# Portier.net
KiCad netlist of a schematic drawn in Altium Designer
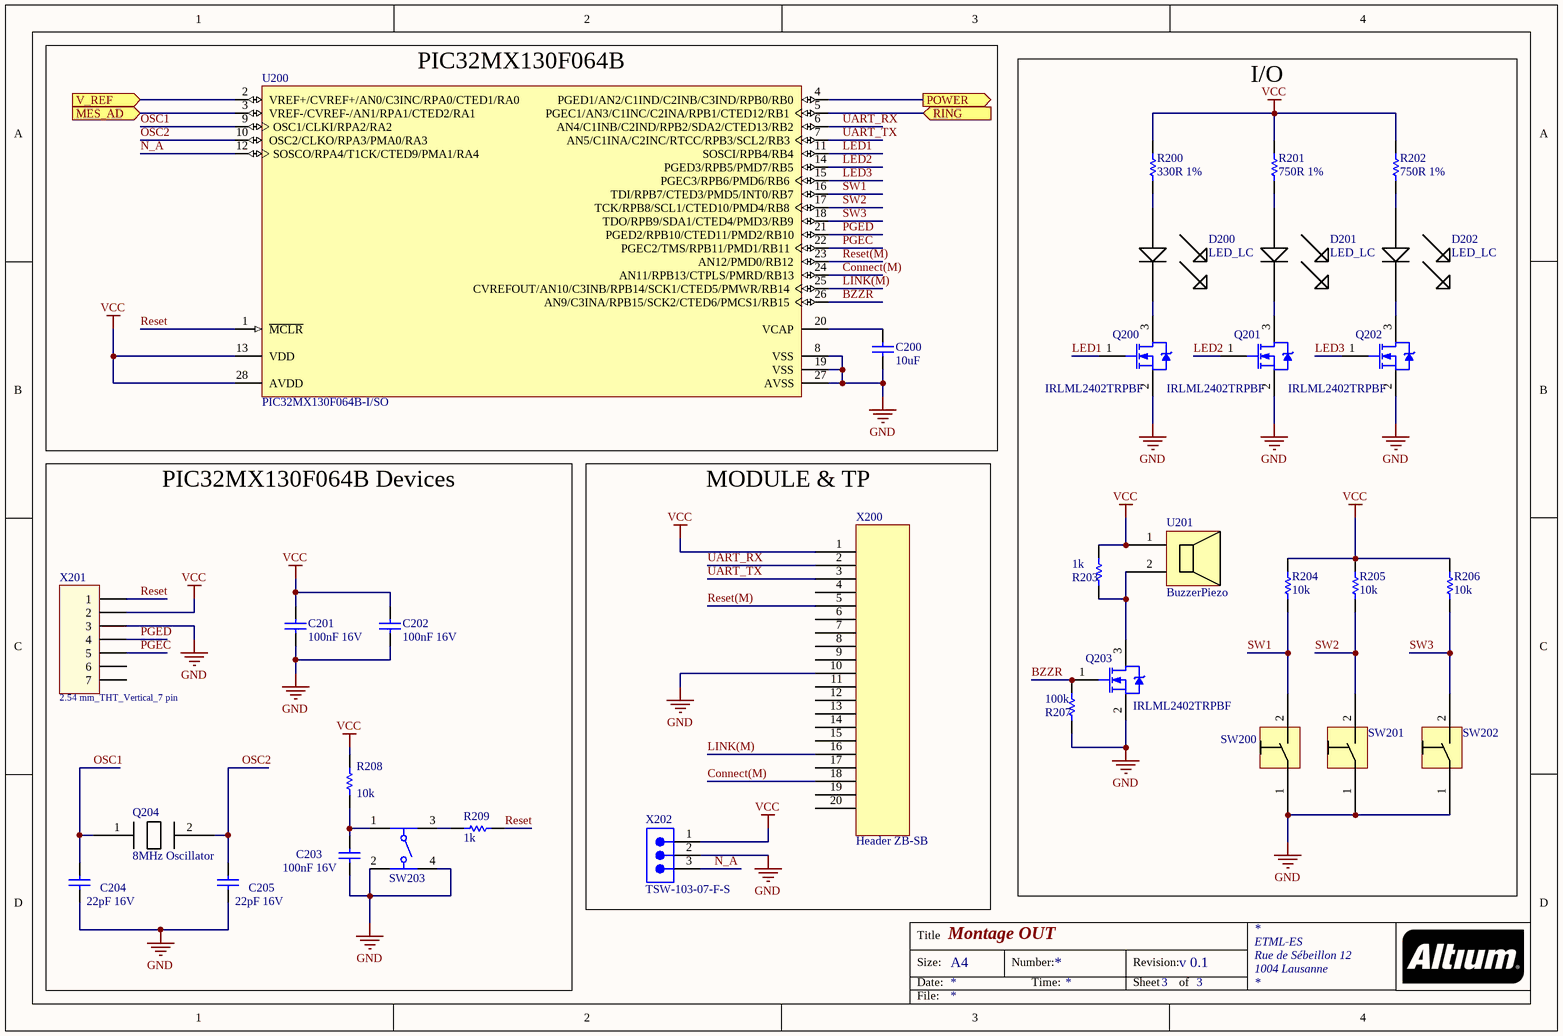
[diagram p0: Portier.SchDoc]

(export (version "E")
  (design (tool "Eeschema 10.0.6"))
  (components
    (comp (ref "C200")
      (value "10uF")
      (footprint "CAPC3216X180X50ML20T25")
      (description "CAP, Ceramic, 10 uF, +/- 10%, 16 V, -55 to 125 degC, 1206 (3216 Metric), RoHS, Tape and Reel")
      (libsource (lib "Altium Content Vault") (part "CMP-1664-00006-1"))
    )
    (comp (ref "C201")
      (value "100nF 16V")
      (footprint "CAPC0805(2012)145_M")
      (description "CAP 100nF 16V ±20% 0805 (2012 Metric) Thickness 1.45mm SMD")
      (libsource (lib "Altium Content Vault") (part "CMP-1036-04404-1"))
    )
    (comp (ref "C202")
      (value "100nF 16V")
      (footprint "CAPC0805(2012)145_M")
      (description "CAP 100nF 16V ±20% 0805 (2012 Metric) Thickness 1.45mm SMD")
      (libsource (lib "Altium Content Vault") (part "CMP-1036-04404-1"))
    )
    (comp (ref "C203")
      (value "100nF 16V")
      (footprint "CAPC0805(2012)145_M")
      (description "CAP 100nF 16V ±20% 0805 (2012 Metric) Thickness 1.45mm SMD")
      (libsource (lib "Altium Content Vault") (part "CMP-1036-04404-1"))
    )
    (comp (ref "C204")
      (value "22pF 16V")
      (footprint "CAPC0805(2012)145_M")
      (description "CAP 22pF 16V ±20% 0805 (2012 Metric) Thickness 1.45mm SMD")
      (libsource (lib "Altium Content Vault") (part "CMP-1036-04404-1"))
    )
    (comp (ref "C205")
      (value "22pF 16V")
      (footprint "CAPC0805(2012)145_M")
      (description "CAP 22pF 16V ±20% 0805 (2012 Metric) Thickness 1.45mm SMD")
      (libsource (lib "Altium Content Vault") (part "CMP-1036-04404-1"))
    )
    (comp (ref "D200")
      (value "LED_LC")
      (footprint "LED_0805")
      (description "LED_LOWCurrent")
      (fields (field (name "MANUFACTURER") "Kingbright") (field (name "PARTNUMBER") "APTD20120LZGCK"))
      (libsource (lib "CircuitOUT") (part "LED LOW CURRENT"))
    )
    (comp (ref "D201")
      (value "LED_LC")
      (footprint "LED_0805")
      (description "LED_LOWCurrent")
      (fields (field (name "MANUFACTURER") "Kingbright") (field (name "PARTNUMBER") "APTD2012LSYCK"))
      (libsource (lib "CircuitOUT") (part "LED LOW CURRENT"))
    )
    (comp (ref "D202")
      (value "LED_LC")
      (footprint "LED_0805")
      (description "LED_LOWCurrent")
      (fields (field (name "MANUFACTURER") "Kingbright") (field (name "PARTNUMBER") "APTD2012LSURCK"))
      (libsource (lib "CircuitOUT") (part "LED LOW CURRENT"))
    )
    (comp (ref "Q200")
      (value "IRLML2402TRPBF")
      (footprint "INTR-IRLML2402TRPBF-3_V")
      (description "HEXFET(R) Power MOSFET, N-Channel, 20 V, 1.2 A, 3-Pin SOT-23, RoHS, Tape and Reel")
      (fields
        (field (name "MANUFACTURER") "Infineon Technologies")
        (field (name "PARTNUMBER") "IRLML2402TRBF")
      )
      (libsource (lib "Altium Content Vault") (part "CMP-2000-05155-1"))
    )
    (comp (ref "Q201")
      (value "IRLML2402TRPBF")
      (footprint "INTR-IRLML2402TRPBF-3_V")
      (description "HEXFET(R) Power MOSFET, N-Channel, 20 V, 1.2 A, 3-Pin SOT-23, RoHS, Tape and Reel")
      (fields
        (field (name "MANUFACTURER") "Infineon Technologies")
        (field (name "PARTNUMBER") "IRLML2402TRBF")
      )
      (libsource (lib "Altium Content Vault") (part "CMP-2000-05155-1"))
    )
    (comp (ref "Q202")
      (value "IRLML2402TRPBF")
      (footprint "INTR-IRLML2402TRPBF-3_V")
      (description "HEXFET(R) Power MOSFET, N-Channel, 20 V, 1.2 A, 3-Pin SOT-23, RoHS, Tape and Reel")
      (fields
        (field (name "MANUFACTURER") "Infineon Technologies")
        (field (name "PARTNUMBER") "IRLML2402TRBF")
      )
      (libsource (lib "Altium Content Vault") (part "CMP-2000-05155-1"))
    )
    (comp (ref "Q203")
      (value "IRLML2402TRPBF")
      (footprint "INTR-IRLML2402TRPBF-3_V")
      (description "HEXFET(R) Power MOSFET, N-Channel, 20 V, 1.2 A, 3-Pin SOT-23, RoHS, Tape and Reel")
      (fields
        (field (name "MANUFACTURER") "Infineon Technologies")
        (field (name "PARTNUMBER") "IRLML2402TRBF")
      )
      (libsource (lib "Altium Content Vault") (part "CMP-2000-05155-1"))
    )
    (comp (ref "Q204")
      (value "8MHz Oscillator")
      (footprint "Oscillator")
      (description "Oscillator 8MHz")
      (fields (field (name "MANUFACTURER") "IQD") (field (name "PARTNUMBER") "LF XTAL003151"))
      (libsource (lib "CircuitOUT") (part "Oscillator 8MHz"))
    )
    (comp (ref "R200")
      (value "330R 1%")
      (footprint "RESC0805(2012)_M")
      (description "330R 0.125W 1% 0805 (2012 Metric)  SMD")
      (libsource (lib "Altium Content Vault") (part "RES"))
    )
    (comp (ref "R201")
      (value "750R 1%")
      (footprint "RESC0805(2012)_N")
      (description "750R 0.125W 1% 0805 (2012 Metric)  SMD")
      (libsource (lib "Altium Content Vault") (part "CMP-1013-00496-1"))
    )
    (comp (ref "R202")
      (value "750R 1%")
      (footprint "RESC0805(2012)_N")
      (description "750R 0.125W 1% 0805 (2012 Metric)  SMD")
      (libsource (lib "Altium Content Vault") (part "CMP-1013-00496-1"))
    )
    (comp (ref "R203")
      (value "1k")
      (footprint "RESC2013X60X35ML10T20")
      (description "Chip Resistor, 1 KOhm, +/- 1%, 125 mW, -55 to 155 degC, 0805 (2012 Metric), RoHS, Tape and Reel")
      (libsource (lib "Altium Content Vault") (part "CMP-2100-03671-1"))
    )
    (comp (ref "R204")
      (value "10k")
      (footprint "RESC2013X60X35NL10T20")
      (description "Chip Resistor, 10 KOhm, +/- 1%, 0.125 W, -55 to 155 degC, 0805 (2012 Metric), RoHS, Tape and Reel")
      (libsource (lib "Altium Content Vault") (part "RES-2"))
    )
    (comp (ref "R205")
      (value "10k")
      (footprint "RESC2013X60X35NL10T20")
      (description "Chip Resistor, 10 KOhm, +/- 1%, 0.125 W, -55 to 155 degC, 0805 (2012 Metric), RoHS, Tape and Reel")
      (libsource (lib "Altium Content Vault") (part "RES-2"))
    )
    (comp (ref "R206")
      (value "10k")
      (footprint "RESC2013X60X35NL10T20")
      (description "Chip Resistor, 10 KOhm, +/- 1%, 0.125 W, -55 to 155 degC, 0805 (2012 Metric), RoHS, Tape and Reel")
      (libsource (lib "Altium Content Vault") (part "RES-2"))
    )
    (comp (ref "R207")
      (value "100k")
      (footprint "RESC2013X60X35ML10T20")
      (description "Chip Resistor, 100 KOhm, +/- 1%, 125 mW, -55 to 155 degC, 0805 (2012 Metric), RoHS, Tape and Reel")
      (libsource (lib "Altium Content Vault") (part "CMP-2100-03671-1"))
    )
    (comp (ref "R208")
      (value "10k")
      (footprint "RESC2013X60X35NL10T20")
      (description "Chip Resistor, 10 KOhm, +/- 1%, 0.125 W, -55 to 155 degC, 0805 (2012 Metric), RoHS, Tape and Reel")
      (libsource (lib "Altium Content Vault") (part "CMP-1659-00011-4"))
    )
    (comp (ref "R209")
      (value "1k")
      (footprint "RESC2013X60X35NL10T20")
      (description "Chip Resistor, 1 KOhm, +/- 1%, 0.125 W, -55 to 155 degC, 0805 (2012 Metric), RoHS, Tape and Reel")
      (libsource (lib "Altium Content Vault") (part "CMP-1659-00011-4"))
    )
    (comp (ref "SW200")
      (value "SW")
      (footprint "Switch_Schurter")
      (description "Switch 12.7x12.7x17.5")
      (fields (field (name "MANUFACTURER") "Schurter"))
      (libsource (lib "CircuitOUT") (part "Switch_Schurter"))
    )
    (comp (ref "SW201")
      (value "SW")
      (footprint "Switch_Schurter")
      (description "Switch 12.7x12.7x17.5")
      (fields (field (name "MANUFACTURER") "Schurter"))
      (libsource (lib "CircuitOUT") (part "Switch_Schurter"))
    )
    (comp (ref "SW202")
      (value "SW")
      (footprint "Switch_Schurter")
      (description "Switch 12.7x12.7x17.5")
      (fields (field (name "MANUFACTURER") "Schurter"))
      (libsource (lib "CircuitOUT") (part "Switch_Schurter"))
    )
    (comp (ref "SW203")
      (value "430152050836")
      (footprint "4301x20508x6_6x6x5")
      (description "WS-TASV 6x6mm Tact Switch, SMD version")
      (fields (field (name "PUBLISHER") "Wurth Elektronik"))
      (libsource (lib "ALTIUM-WS-TASV") (part "430152050836"))
    )
    (comp (ref "U200")
      (value "PIC32MX130F064B-I/SO")
      (footprint "MCHP-SOIC-SO28_L")
      (fields (field (name "MANUFACTURER") "Microchip"))
      (libsource (lib "Altium Content Vault") (part "MCHP-PIC32MX1X0FXXXB-28"))
    )
    (comp (ref "U201")
      (value "BuzzerPiezo")
      (footprint "Buzzer")
      (description "Buzzer 12mm piezo")
      (fields (field (name "MANUFACTURER") "TDK Corporation") (field (name "PARTNUMBER") "PS1240P02BT"))
      (libsource (lib "CircuitOUT") (part "BZR"))
    )
    (comp (ref "X200")
      (value "Header ZB-SB")
      (footprint "ZB-SB")
      (description "Header 2x10")
      (libsource (lib "CircuitOUT") (part "HDR ZB-SB 2x10"))
    )
    (comp (ref "X201")
      (value "2.54 mm_THT_Vertical_7 pin")
      (footprint "61300711121")
      (description "Pin Header WR-PHD, pitch 2.54 mm, THT, Vertical, single row, 7 pin")
      (fields (field (name "PART NUMBER") "61300711121") (field (name "PUBLISHER") "Wurth Elektronik"))
      (libsource (lib "ALTIUM-PHD_2_54_THT_PIN_HEADER_6130XX11121-rev18a") (part "61300711121"))
    )
    (comp (ref "X202")
      (value "TSW-103-07-F-S")
      (footprint "SMTC-TSW-103-07-X-S")
      (description "0.025\" SQ Post Header, Through-hole, Vertical, -55 to 125 degC, 2.54 mm Pitch, 3-Pin, Male, RoHS")
      (fields (field (name "MANUFACTURER") "Samtec"))
      (libsource (lib "Altium Content Vault") (part "CMP-1024-00331-1"))
    )
  )
  (nets
    (net (code "1") (name "/BZZR") (class "Default")
      (node (ref "Q203") (pin "1") (pinfunction "G_1") (pintype "passive"))
      (node (ref "R207") (pin "2") (pinfunction "2_2") (pintype "passive"))
      (node (ref "U200") (pin "26") (pinfunction "AN9/C3INA/RPB15/SCK2/CTED6/PMCS1/RB15_26") (pintype "bidirectional"))
    )
    (net (code "2") (name "/Connect(M)") (class "Default")
      (node (ref "U200") (pin "24") (pinfunction "AN11/RPB13/CTPLS/PMRD/RB13_24") (pintype "bidirectional"))
      (node (ref "X200") (pin "18") (pintype "passive"))
    )
    (net (code "3") (name "/LED1") (class "Default")
      (node (ref "Q200") (pin "1") (pinfunction "G_1") (pintype "passive"))
      (node (ref "U200") (pin "11") (pinfunction "SOSCI/RPB4/RB4_11") (pintype "bidirectional"))
    )
    (net (code "4") (name "/LED2") (class "Default")
      (node (ref "Q201") (pin "1") (pinfunction "G_1") (pintype "passive"))
      (node (ref "U200") (pin "14") (pinfunction "PGED3/RPB5/PMD7/RB5_14") (pintype "bidirectional"))
    )
    (net (code "5") (name "/LED3") (class "Default")
      (node (ref "Q202") (pin "1") (pinfunction "G_1") (pintype "passive"))
      (node (ref "U200") (pin "15") (pinfunction "PGEC3/RPB6/PMD6/RB6_15") (pintype "bidirectional"))
    )
    (net (code "6") (name "/LINK(M)") (class "Default")
      (node (ref "U200") (pin "25") (pinfunction "CVREFOUT/AN10/C3INB/RPB14/SCK1/CTED5/PMWR/RB14_25") (pintype "bidirectional"))
      (node (ref "X200") (pin "16") (pintype "passive"))
    )
    (net (code "7") (name "/MES_AD") (class "Default")
      (node (ref "U200") (pin "3") (pinfunction "VREF-/CVREF-/AN1/RPA1/CTED2/RA1_3") (pintype "bidirectional"))
    )
    (net (code "8") (name "/N_A") (class "Default")
      (node (ref "U200") (pin "12") (pinfunction "SOSCO/RPA4/T1CK/CTED9/PMA1/RA4_12") (pintype "bidirectional"))
      (node (ref "X202") (pin "3") (pinfunction "3_3") (pintype "passive"))
    )
    (net (code "9") (name "/OSC1") (class "Default")
      (node (ref "C204") (pin "2") (pinfunction "2_2") (pintype "passive"))
      (node (ref "Q204") (pin "1") (pintype "passive"))
      (node (ref "U200") (pin "9") (pinfunction "OSC1/CLKI/RPA2/RA2_9") (pintype "bidirectional"))
    )
    (net (code "10") (name "/OSC2") (class "Default")
      (node (ref "C205") (pin "2") (pinfunction "2_2") (pintype "passive"))
      (node (ref "Q204") (pin "2") (pintype "passive"))
      (node (ref "U200") (pin "10") (pinfunction "OSC2/CLKO/RPA3/PMA0/RA3_10") (pintype "bidirectional"))
    )
    (net (code "11") (name "/PGEC") (class "Default")
      (node (ref "U200") (pin "22") (pinfunction "PGEC2/TMS/RPB11/PMD1/RB11_22") (pintype "bidirectional"))
      (node (ref "X201") (pin "5") (pinfunction "5_5") (pintype "passive"))
    )
    (net (code "12") (name "/PGED") (class "Default")
      (node (ref "U200") (pin "21") (pinfunction "PGED2/RPB10/CTED11/PMD2/RB10_21") (pintype "bidirectional"))
      (node (ref "X201") (pin "4") (pinfunction "4_4") (pintype "passive"))
    )
    (net (code "13") (name "/POWER") (class "Default")
      (node (ref "U200") (pin "4") (pinfunction "PGED1/AN2/C1IND/C2INB/C3IND/RPB0/RB0_4") (pintype "bidirectional"))
    )
    (net (code "14") (name "/RING") (class "Default")
      (node (ref "U200") (pin "5") (pinfunction "PGEC1/AN3/C1INC/C2INA/RPB1/CTED12/RB1_5") (pintype "bidirectional"))
    )
    (net (code "15") (name "/Reset") (class "Default")
      (node (ref "R209") (pin "2") (pinfunction "2_2") (pintype "passive"))
      (node (ref "U200") (pin "1") (pinfunction "~{MCLR}_1") (pintype "input"))
      (node (ref "X201") (pin "1") (pinfunction "1_1") (pintype "passive"))
    )
    (net (code "16") (name "/Reset(M)") (class "Default")
      (node (ref "U200") (pin "23") (pinfunction "AN12/PMD0/RB12_23") (pintype "bidirectional"))
      (node (ref "X200") (pin "5") (pintype "passive"))
    )
    (net (code "17") (name "/SW1") (class "Default")
      (node (ref "R204") (pin "1") (pinfunction "1_1") (pintype "passive"))
      (node (ref "SW200") (pin "2") (pinfunction "2_2") (pintype "passive"))
      (node (ref "U200") (pin "16") (pinfunction "TDI/RPB7/CTED3/PMD5/INT0/RB7_16") (pintype "bidirectional"))
    )
    (net (code "18") (name "/SW2") (class "Default")
      (node (ref "R205") (pin "1") (pinfunction "1_1") (pintype "passive"))
      (node (ref "SW201") (pin "2") (pinfunction "2_2") (pintype "passive"))
      (node (ref "U200") (pin "17") (pinfunction "TCK/RPB8/SCL1/CTED10/PMD4/RB8_17") (pintype "bidirectional"))
    )
    (net (code "19") (name "/SW3") (class "Default")
      (node (ref "R206") (pin "1") (pinfunction "1_1") (pintype "passive"))
      (node (ref "SW202") (pin "2") (pinfunction "2_2") (pintype "passive"))
      (node (ref "U200") (pin "18") (pinfunction "TDO/RPB9/SDA1/CTED4/PMD3/RB9_18") (pintype "bidirectional"))
    )
    (net (code "20") (name "/UART_RX") (class "Default")
      (node (ref "U200") (pin "6") (pinfunction "AN4/C1INB/C2IND/RPB2/SDA2/CTED13/RB2_6") (pintype "bidirectional"))
      (node (ref "X200") (pin "2") (pintype "passive"))
    )
    (net (code "21") (name "/UART_TX") (class "Default")
      (node (ref "U200") (pin "7") (pinfunction "AN5/C1INA/C2INC/RTCC/RPB3/SCL2/RB3_7") (pintype "bidirectional"))
      (node (ref "X200") (pin "3") (pintype "passive"))
    )
    (net (code "22") (name "/V_REF") (class "Default")
      (node (ref "U200") (pin "2") (pinfunction "VREF+/CVREF+/AN0/C3INC/RPA0/CTED1/RA0_2") (pintype "bidirectional"))
    )
    (net (code "23") (name "GND") (class "Default")
      (node (ref "C200") (pin "2") (pinfunction "2_2") (pintype "passive"))
      (node (ref "C201") (pin "1") (pinfunction "1_1") (pintype "passive"))
      (node (ref "C202") (pin "1") (pinfunction "1_1") (pintype "passive"))
      (node (ref "C203") (pin "1") (pinfunction "1_1") (pintype "passive"))
      (node (ref "C204") (pin "1") (pinfunction "1_1") (pintype "passive"))
      (node (ref "C205") (pin "1") (pinfunction "1_1") (pintype "passive"))
      (node (ref "Q200") (pin "2") (pinfunction "S_2") (pintype "passive"))
      (node (ref "Q201") (pin "2") (pinfunction "S_2") (pintype "passive"))
      (node (ref "Q202") (pin "2") (pinfunction "S_2") (pintype "passive"))
      (node (ref "Q203") (pin "2") (pinfunction "S_2") (pintype "passive"))
      (node (ref "R207") (pin "1") (pinfunction "1_1") (pintype "passive"))
      (node (ref "SW200") (pin "1") (pinfunction "1_1") (pintype "passive"))
      (node (ref "SW201") (pin "1") (pinfunction "1_1") (pintype "passive"))
      (node (ref "SW202") (pin "1") (pinfunction "1_1") (pintype "passive"))
      (node (ref "SW203") (pin "2") (pinfunction "2_2") (pintype "passive"))
      (node (ref "SW203") (pin "4") (pinfunction "4_4") (pintype "passive"))
      (node (ref "U200") (pin "19") (pinfunction "VSS_19") (pintype "power_in"))
      (node (ref "U200") (pin "27") (pinfunction "AVSS_27") (pintype "power_in"))
      (node (ref "U200") (pin "8") (pinfunction "VSS_8") (pintype "power_in"))
      (node (ref "X200") (pin "10") (pintype "passive"))
      (node (ref "X201") (pin "3") (pinfunction "3_3") (pintype "passive"))
      (node (ref "X202") (pin "2") (pinfunction "2_2") (pintype "passive"))
    )
    (net (code "24") (name "Net-(C203-Pad2)") (class "Default")
      (node (ref "C203") (pin "2") (pinfunction "2_2") (pintype "passive"))
      (node (ref "R208") (pin "2") (pinfunction "2_2") (pintype "passive"))
      (node (ref "SW203") (pin "1") (pinfunction "1_1") (pintype "passive"))
    )
    (net (code "25") (name "Net-(D200-A)") (class "Default")
      (node (ref "D200") (pin "1") (pinfunction "A_1") (pintype "passive"))
      (node (ref "R200") (pin "1") (pinfunction "1_1") (pintype "passive"))
    )
    (net (code "26") (name "Net-(D200-K)") (class "Default")
      (node (ref "D200") (pin "2") (pinfunction "K_2") (pintype "passive"))
      (node (ref "Q200") (pin "3") (pinfunction "D_3") (pintype "passive"))
    )
    (net (code "27") (name "Net-(D201-A)") (class "Default")
      (node (ref "D201") (pin "1") (pinfunction "A_1") (pintype "passive"))
      (node (ref "R201") (pin "2") (pinfunction "2_2") (pintype "passive"))
    )
    (net (code "28") (name "Net-(D201-K)") (class "Default")
      (node (ref "D201") (pin "2") (pinfunction "K_2") (pintype "passive"))
      (node (ref "Q201") (pin "3") (pinfunction "D_3") (pintype "passive"))
    )
    (net (code "29") (name "Net-(D202-A)") (class "Default")
      (node (ref "D202") (pin "1") (pinfunction "A_1") (pintype "passive"))
      (node (ref "R202") (pin "1") (pinfunction "1_1") (pintype "passive"))
    )
    (net (code "30") (name "Net-(D202-K)") (class "Default")
      (node (ref "D202") (pin "2") (pinfunction "K_2") (pintype "passive"))
      (node (ref "Q202") (pin "3") (pinfunction "D_3") (pintype "passive"))
    )
    (net (code "31") (name "Net-(Q203-D)") (class "Default")
      (node (ref "Q203") (pin "3") (pinfunction "D_3") (pintype "passive"))
      (node (ref "R203") (pin "1") (pinfunction "1_1") (pintype "passive"))
      (node (ref "U201") (pin "2") (pintype "passive"))
    )
    (net (code "32") (name "Net-(R209-Pad1)") (class "Default")
      (node (ref "R209") (pin "1") (pinfunction "1_1") (pintype "passive"))
      (node (ref "SW203") (pin "3") (pinfunction "3_3") (pintype "passive"))
    )
    (net (code "33") (name "Net-(U200-VCAP)") (class "Default")
      (node (ref "C200") (pin "1") (pinfunction "1_1") (pintype "passive"))
      (node (ref "U200") (pin "20") (pinfunction "VCAP_20") (pintype "passive"))
    )
    (net (code "34") (name "VCC") (class "Default")
      (node (ref "C201") (pin "2") (pinfunction "2_2") (pintype "passive"))
      (node (ref "C202") (pin "2") (pinfunction "2_2") (pintype "passive"))
      (node (ref "R200") (pin "2") (pinfunction "2_2") (pintype "passive"))
      (node (ref "R201") (pin "1") (pinfunction "1_1") (pintype "passive"))
      (node (ref "R202") (pin "2") (pinfunction "2_2") (pintype "passive"))
      (node (ref "R203") (pin "2") (pinfunction "2_2") (pintype "passive"))
      (node (ref "R204") (pin "2") (pinfunction "2_2") (pintype "passive"))
      (node (ref "R205") (pin "2") (pinfunction "2_2") (pintype "passive"))
      (node (ref "R206") (pin "2") (pinfunction "2_2") (pintype "passive"))
      (node (ref "R208") (pin "1") (pinfunction "1_1") (pintype "passive"))
      (node (ref "U200") (pin "13") (pinfunction "VDD_13") (pintype "power_in"))
      (node (ref "U200") (pin "28") (pinfunction "AVDD_28") (pintype "power_in"))
      (node (ref "U201") (pin "1") (pintype "passive"))
      (node (ref "X200") (pin "1") (pintype "passive"))
      (node (ref "X201") (pin "2") (pinfunction "2_2") (pintype "passive"))
      (node (ref "X202") (pin "1") (pinfunction "1_1") (pintype "passive"))
    )
    (net (code "35") (name "unconnected-(X200-Pad4)") (class "Default")
      (node (ref "X200") (pin "4") (pintype "passive"))
    )
    (net (code "36") (name "unconnected-(X200-Pad6)") (class "Default")
      (node (ref "X200") (pin "6") (pintype "passive"))
    )
    (net (code "37") (name "unconnected-(X200-Pad7)") (class "Default")
      (node (ref "X200") (pin "7") (pintype "passive"))
    )
    (net (code "38") (name "unconnected-(X200-Pad8)") (class "Default")
      (node (ref "X200") (pin "8") (pintype "passive"))
    )
    (net (code "39") (name "unconnected-(X200-Pad9)") (class "Default")
      (node (ref "X200") (pin "9") (pintype "passive"))
    )
    (net (code "40") (name "unconnected-(X200-Pad11)") (class "Default")
      (node (ref "X200") (pin "11") (pintype "passive"))
    )
    (net (code "41") (name "unconnected-(X200-Pad12)") (class "Default")
      (node (ref "X200") (pin "12") (pintype "passive"))
    )
    (net (code "42") (name "unconnected-(X200-Pad13)") (class "Default")
      (node (ref "X200") (pin "13") (pintype "passive"))
    )
    (net (code "43") (name "unconnected-(X200-Pad14)") (class "Default")
      (node (ref "X200") (pin "14") (pintype "passive"))
    )
    (net (code "44") (name "unconnected-(X200-Pad15)") (class "Default")
      (node (ref "X200") (pin "15") (pintype "passive"))
    )
    (net (code "45") (name "unconnected-(X200-Pad17)") (class "Default")
      (node (ref "X200") (pin "17") (pintype "passive"))
    )
    (net (code "46") (name "unconnected-(X200-Pad19)") (class "Default")
      (node (ref "X200") (pin "19") (pintype "passive"))
    )
    (net (code "47") (name "unconnected-(X200-Pad20)") (class "Default")
      (node (ref "X200") (pin "20") (pintype "passive"))
    )
    (net (code "48") (name "unconnected-(X201-Pad6)") (class "Default")
      (node (ref "X201") (pin "6") (pinfunction "6_6") (pintype "passive"))
    )
    (net (code "49") (name "unconnected-(X201-Pad7)") (class "Default")
      (node (ref "X201") (pin "7") (pinfunction "7_7") (pintype "passive"))
    )
  )
)
